# main.net
KiCad netlist of a schematic drawn in Altium Designer
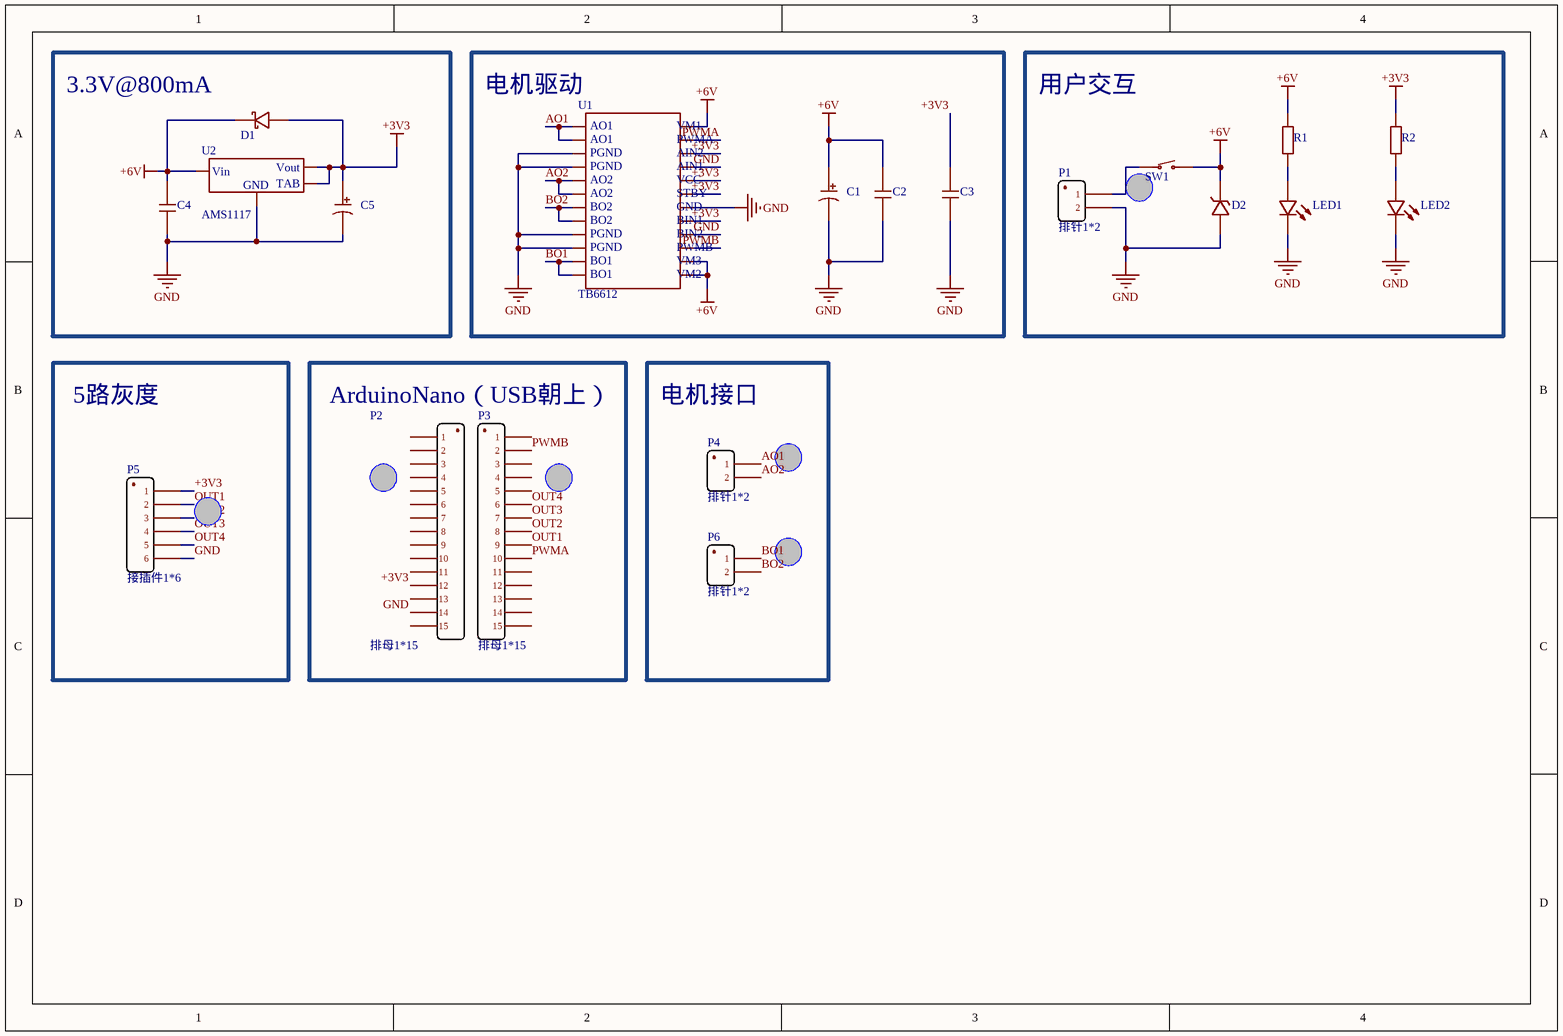
[diagram p0: main.SchDoc]

(export (version "E")
  (design (tool "Eeschema 10.0.6"))
  (components
    (comp (ref "C1") (value "10uF") (footprint "3528B/1210") (libsource (lib "元件库") (part "电容_贴片钽")))
    (comp (ref "C2") (value "0.1uF") (footprint "0805C") (libsource (lib "元件库") (part "电容_贴片")))
    (comp (ref "C3") (value "0.1uF") (footprint "0805C") (libsource (lib "元件库") (part "电容_贴片")))
    (comp (ref "C4") (value "10uF") (footprint "0603C") (libsource (lib "元件库") (part "电容_贴片")))
    (comp (ref "C5") (value "100uF") (footprint "3528B/1210") (libsource (lib "元件库") (part "电容_贴片钽")))
    (comp (ref "D1") (value "SS34") (footprint "SMA") (libsource (lib "元件库") (part "二极管_肖特基")))
    (comp (ref "D2") (value "瞬态抑制二极管") (footprint "SMA") (libsource (lib "元件库") (part "二极管_瞬态抑制")))
    (comp (ref "LED1") (value "LED") (footprint "0603D") (libsource (lib "元件库") (part "二极管_贴片发光")))
    (comp (ref "LED2") (value "LED") (footprint "0603D") (libsource (lib "元件库") (part "二极管_贴片发光")))
    (comp (ref "P1") (value "排针1*2") (footprint "Pin-PB-M-1*2") (libsource (lib "接口库") (part "接插件1*2")))
    (comp (ref "P2") (value "排母1*15") (footprint "Pin-PB-F-1*15") (libsource (lib "接口库") (part "接插件1*15")))
    (comp (ref "P3") (value "排母1*15") (footprint "Pin-PB-F-1*15") (libsource (lib "") (part "接插件1*15_1")))
    (comp (ref "P4") (value "排针1*2") (footprint "Pin-PB-M-1*2") (libsource (lib "接口库") (part "接插件1*2")))
    (comp (ref "P5") (value "接插件1*6") (footprint "XH2.54_AW_1*6") (libsource (lib "接口库") (part "接插件1*6")))
    (comp (ref "P6") (value "排针1*2") (footprint "Pin-PB-M-1*2") (libsource (lib "接口库") (part "接插件1*2")))
    (comp (ref "R1") (value "4K7") (footprint "0603R") (libsource (lib "元件库") (part "电阻_贴片")))
    (comp (ref "R2") (value "4K7") (footprint "0603R") (libsource (lib "元件库") (part "电阻_贴片")))
    (comp (ref "SW1") (value "开关") (footprint "*SW-5.08mm") (libsource (lib "元件库") (part "开关_二脚")))
    (comp (ref "U1") (value "TB6612") (footprint "SSOP24") (libsource (lib "元件库") (part "芯片/IC-电机驱动-TB6612")))
    (comp (ref "U2")
      (value "AMS1117")
      (footprint "SOT-223")
      (libsource (lib "元件库") (part "芯片/IC-线性稳压管-AMS1117"))
    )
  )
  (nets
    (net (code "1") (name "+3V3") (class "Default")
      (node (ref "C3") (pin "2") (pinfunction "2_2") (pintype "passive"))
      (node (ref "C5") (pin "1") (pinfunction "1_1") (pintype "passive"))
      (node (ref "D1") (pin "1") (pinfunction "1_1") (pintype "passive"))
      (node (ref "P2") (pin "12") (pinfunction "12_12") (pintype "passive"))
      (node (ref "P5") (pin "1") (pinfunction "1_1") (pintype "passive"))
      (node (ref "R2") (pin "2") (pinfunction "2_2") (pintype "passive"))
      (node (ref "U1") (pin "17") (pintype "passive"))
      (node (ref "U1") (pin "19") (pintype "passive"))
      (node (ref "U1") (pin "20") (pintype "passive"))
      (node (ref "U1") (pin "22") (pintype "passive"))
      (node (ref "U2") (pin "2") (pinfunction "2_2") (pintype "passive"))
      (node (ref "U2") (pin "4") (pinfunction "4_4") (pintype "passive"))
    )
    (net (code "2") (name "+6V") (class "Default")
      (node (ref "C1") (pin "1") (pinfunction "1_1") (pintype "passive"))
      (node (ref "C2") (pin "2") (pinfunction "2_2") (pintype "passive"))
      (node (ref "C4") (pin "2") (pinfunction "2_2") (pintype "passive"))
      (node (ref "D1") (pin "2") (pinfunction "2_2") (pintype "passive"))
      (node (ref "D2") (pin "2") (pinfunction "2_2") (pintype "passive"))
      (node (ref "R1") (pin "2") (pinfunction "2_2") (pintype "passive"))
      (node (ref "SW1") (pin "2") (pinfunction "2_2") (pintype "passive"))
      (node (ref "U1") (pin "13") (pintype "passive"))
      (node (ref "U1") (pin "14") (pintype "passive"))
      (node (ref "U1") (pin "24") (pintype "passive"))
      (node (ref "U2") (pin "3") (pinfunction "3_3") (pintype "passive"))
    )
    (net (code "3") (name "/AO1") (class "Default")
      (node (ref "P4") (pin "1") (pinfunction "1_1") (pintype "passive"))
      (node (ref "U1") (pin "1") (pintype "passive"))
      (node (ref "U1") (pin "2") (pintype "passive"))
    )
    (net (code "4") (name "/AO2") (class "Default")
      (node (ref "P4") (pin "2") (pinfunction "2_2") (pintype "passive"))
      (node (ref "U1") (pin "5") (pintype "passive"))
      (node (ref "U1") (pin "6") (pintype "passive"))
    )
    (net (code "5") (name "/BO1") (class "Default")
      (node (ref "P6") (pin "1") (pinfunction "1_1") (pintype "passive"))
      (node (ref "U1") (pin "11") (pintype "passive"))
      (node (ref "U1") (pin "12") (pintype "passive"))
    )
    (net (code "6") (name "/BO2") (class "Default")
      (node (ref "P6") (pin "2") (pinfunction "2_2") (pintype "passive"))
      (node (ref "U1") (pin "7") (pintype "passive"))
      (node (ref "U1") (pin "8") (pintype "passive"))
    )
    (net (code "7") (name "/OUT1") (class "Default")
      (node (ref "P3") (pin "9") (pinfunction "9_9") (pintype "passive"))
      (node (ref "P5") (pin "2") (pinfunction "2_2") (pintype "passive"))
    )
    (net (code "8") (name "/OUT2") (class "Default")
      (node (ref "P3") (pin "8") (pinfunction "8_8") (pintype "passive"))
      (node (ref "P5") (pin "3") (pinfunction "3_3") (pintype "passive"))
    )
    (net (code "9") (name "/OUT3") (class "Default")
      (node (ref "P3") (pin "7") (pinfunction "7_7") (pintype "passive"))
      (node (ref "P5") (pin "4") (pinfunction "4_4") (pintype "passive"))
    )
    (net (code "10") (name "/OUT4") (class "Default")
      (node (ref "P3") (pin "6") (pinfunction "6_6") (pintype "passive"))
      (node (ref "P5") (pin "5") (pinfunction "5_5") (pintype "passive"))
    )
    (net (code "11") (name "/PWMA") (class "Default")
      (node (ref "P3") (pin "10") (pinfunction "10_10") (pintype "passive"))
      (node (ref "U1") (pin "23") (pintype "passive"))
    )
    (net (code "12") (name "/PWMB") (class "Default")
      (node (ref "P3") (pin "2") (pinfunction "2_2") (pintype "passive"))
      (node (ref "U1") (pin "15") (pintype "passive"))
    )
    (net (code "13") (name "GND") (class "Default")
      (node (ref "C1") (pin "2") (pinfunction "2_2") (pintype "passive"))
      (node (ref "C2") (pin "1") (pinfunction "1_1") (pintype "passive"))
      (node (ref "C3") (pin "1") (pinfunction "1_1") (pintype "passive"))
      (node (ref "C4") (pin "1") (pinfunction "1_1") (pintype "passive"))
      (node (ref "C5") (pin "2") (pinfunction "2_2") (pintype "passive"))
      (node (ref "D2") (pin "1") (pinfunction "1_1") (pintype "passive"))
      (node (ref "LED1") (pin "2") (pinfunction "2_2") (pintype "passive"))
      (node (ref "LED2") (pin "2") (pinfunction "2_2") (pintype "passive"))
      (node (ref "P1") (pin "2") (pinfunction "2_2") (pintype "passive"))
      (node (ref "P2") (pin "14") (pinfunction "14_14") (pintype "passive"))
      (node (ref "P5") (pin "6") (pinfunction "6_6") (pintype "passive"))
      (node (ref "U1") (pin "10") (pintype "passive"))
      (node (ref "U1") (pin "16") (pintype "passive"))
      (node (ref "U1") (pin "18") (pintype "passive"))
      (node (ref "U1") (pin "21") (pintype "passive"))
      (node (ref "U1") (pin "3") (pintype "passive"))
      (node (ref "U1") (pin "4") (pintype "passive"))
      (node (ref "U1") (pin "9") (pintype "passive"))
      (node (ref "U2") (pin "1") (pinfunction "1_1") (pintype "passive"))
    )
    (net (code "14") (name "Net-(LED1-Pad1)") (class "Default")
      (node (ref "LED1") (pin "1") (pinfunction "1_1") (pintype "passive"))
      (node (ref "R1") (pin "1") (pinfunction "1_1") (pintype "passive"))
    )
    (net (code "15") (name "Net-(LED2-Pad1)") (class "Default")
      (node (ref "LED2") (pin "1") (pinfunction "1_1") (pintype "passive"))
      (node (ref "R2") (pin "1") (pinfunction "1_1") (pintype "passive"))
    )
    (net (code "16") (name "Net-(P1-Pad1)") (class "Default")
      (node (ref "P1") (pin "1") (pinfunction "1_1") (pintype "passive"))
      (node (ref "SW1") (pin "1") (pinfunction "1_1") (pintype "passive"))
    )
    (net (code "17") (name "unconnected-(P2-Pad1)") (class "Default")
      (node (ref "P2") (pin "1") (pinfunction "1_1") (pintype "passive"))
    )
    (net (code "18") (name "unconnected-(P2-Pad2)") (class "Default")
      (node (ref "P2") (pin "2") (pinfunction "2_2") (pintype "passive"))
    )
    (net (code "19") (name "unconnected-(P2-Pad3)") (class "Default")
      (node (ref "P2") (pin "3") (pinfunction "3_3") (pintype "passive"))
    )
    (net (code "20") (name "unconnected-(P2-Pad4)") (class "Default")
      (node (ref "P2") (pin "4") (pinfunction "4_4") (pintype "passive"))
    )
    (net (code "21") (name "unconnected-(P2-Pad5)") (class "Default")
      (node (ref "P2") (pin "5") (pinfunction "5_5") (pintype "passive"))
    )
    (net (code "22") (name "unconnected-(P2-Pad6)") (class "Default")
      (node (ref "P2") (pin "6") (pinfunction "6_6") (pintype "passive"))
    )
    (net (code "23") (name "unconnected-(P2-Pad7)") (class "Default")
      (node (ref "P2") (pin "7") (pinfunction "7_7") (pintype "passive"))
    )
    (net (code "24") (name "unconnected-(P2-Pad8)") (class "Default")
      (node (ref "P2") (pin "8") (pinfunction "8_8") (pintype "passive"))
    )
    (net (code "25") (name "unconnected-(P2-Pad9)") (class "Default")
      (node (ref "P2") (pin "9") (pinfunction "9_9") (pintype "passive"))
    )
    (net (code "26") (name "unconnected-(P2-Pad10)") (class "Default")
      (node (ref "P2") (pin "10") (pinfunction "10_10") (pintype "passive"))
    )
    (net (code "27") (name "unconnected-(P2-Pad11)") (class "Default")
      (node (ref "P2") (pin "11") (pinfunction "11_11") (pintype "passive"))
    )
    (net (code "28") (name "unconnected-(P2-Pad13)") (class "Default")
      (node (ref "P2") (pin "13") (pinfunction "13_13") (pintype "passive"))
    )
    (net (code "29") (name "unconnected-(P2-Pad15)") (class "Default")
      (node (ref "P2") (pin "15") (pinfunction "15_15") (pintype "passive"))
    )
    (net (code "30") (name "unconnected-(P3-Pad1)") (class "Default")
      (node (ref "P3") (pin "1") (pinfunction "1_1") (pintype "passive"))
    )
    (net (code "31") (name "unconnected-(P3-Pad3)") (class "Default")
      (node (ref "P3") (pin "3") (pinfunction "3_3") (pintype "passive"))
    )
    (net (code "32") (name "unconnected-(P3-Pad4)") (class "Default")
      (node (ref "P3") (pin "4") (pinfunction "4_4") (pintype "passive"))
    )
    (net (code "33") (name "unconnected-(P3-Pad5)") (class "Default")
      (node (ref "P3") (pin "5") (pinfunction "5_5") (pintype "passive"))
    )
    (net (code "34") (name "unconnected-(P3-Pad11)") (class "Default")
      (node (ref "P3") (pin "11") (pinfunction "11_11") (pintype "passive"))
    )
    (net (code "35") (name "unconnected-(P3-Pad12)") (class "Default")
      (node (ref "P3") (pin "12") (pinfunction "12_12") (pintype "passive"))
    )
    (net (code "36") (name "unconnected-(P3-Pad13)") (class "Default")
      (node (ref "P3") (pin "13") (pinfunction "13_13") (pintype "passive"))
    )
    (net (code "37") (name "unconnected-(P3-Pad14)") (class "Default")
      (node (ref "P3") (pin "14") (pinfunction "14_14") (pintype "passive"))
    )
    (net (code "38") (name "unconnected-(P3-Pad15)") (class "Default")
      (node (ref "P3") (pin "15") (pinfunction "15_15") (pintype "passive"))
    )
  )
)
